# FanControllerv10.net
KiCad netlist of a schematic drawn in EAGLE
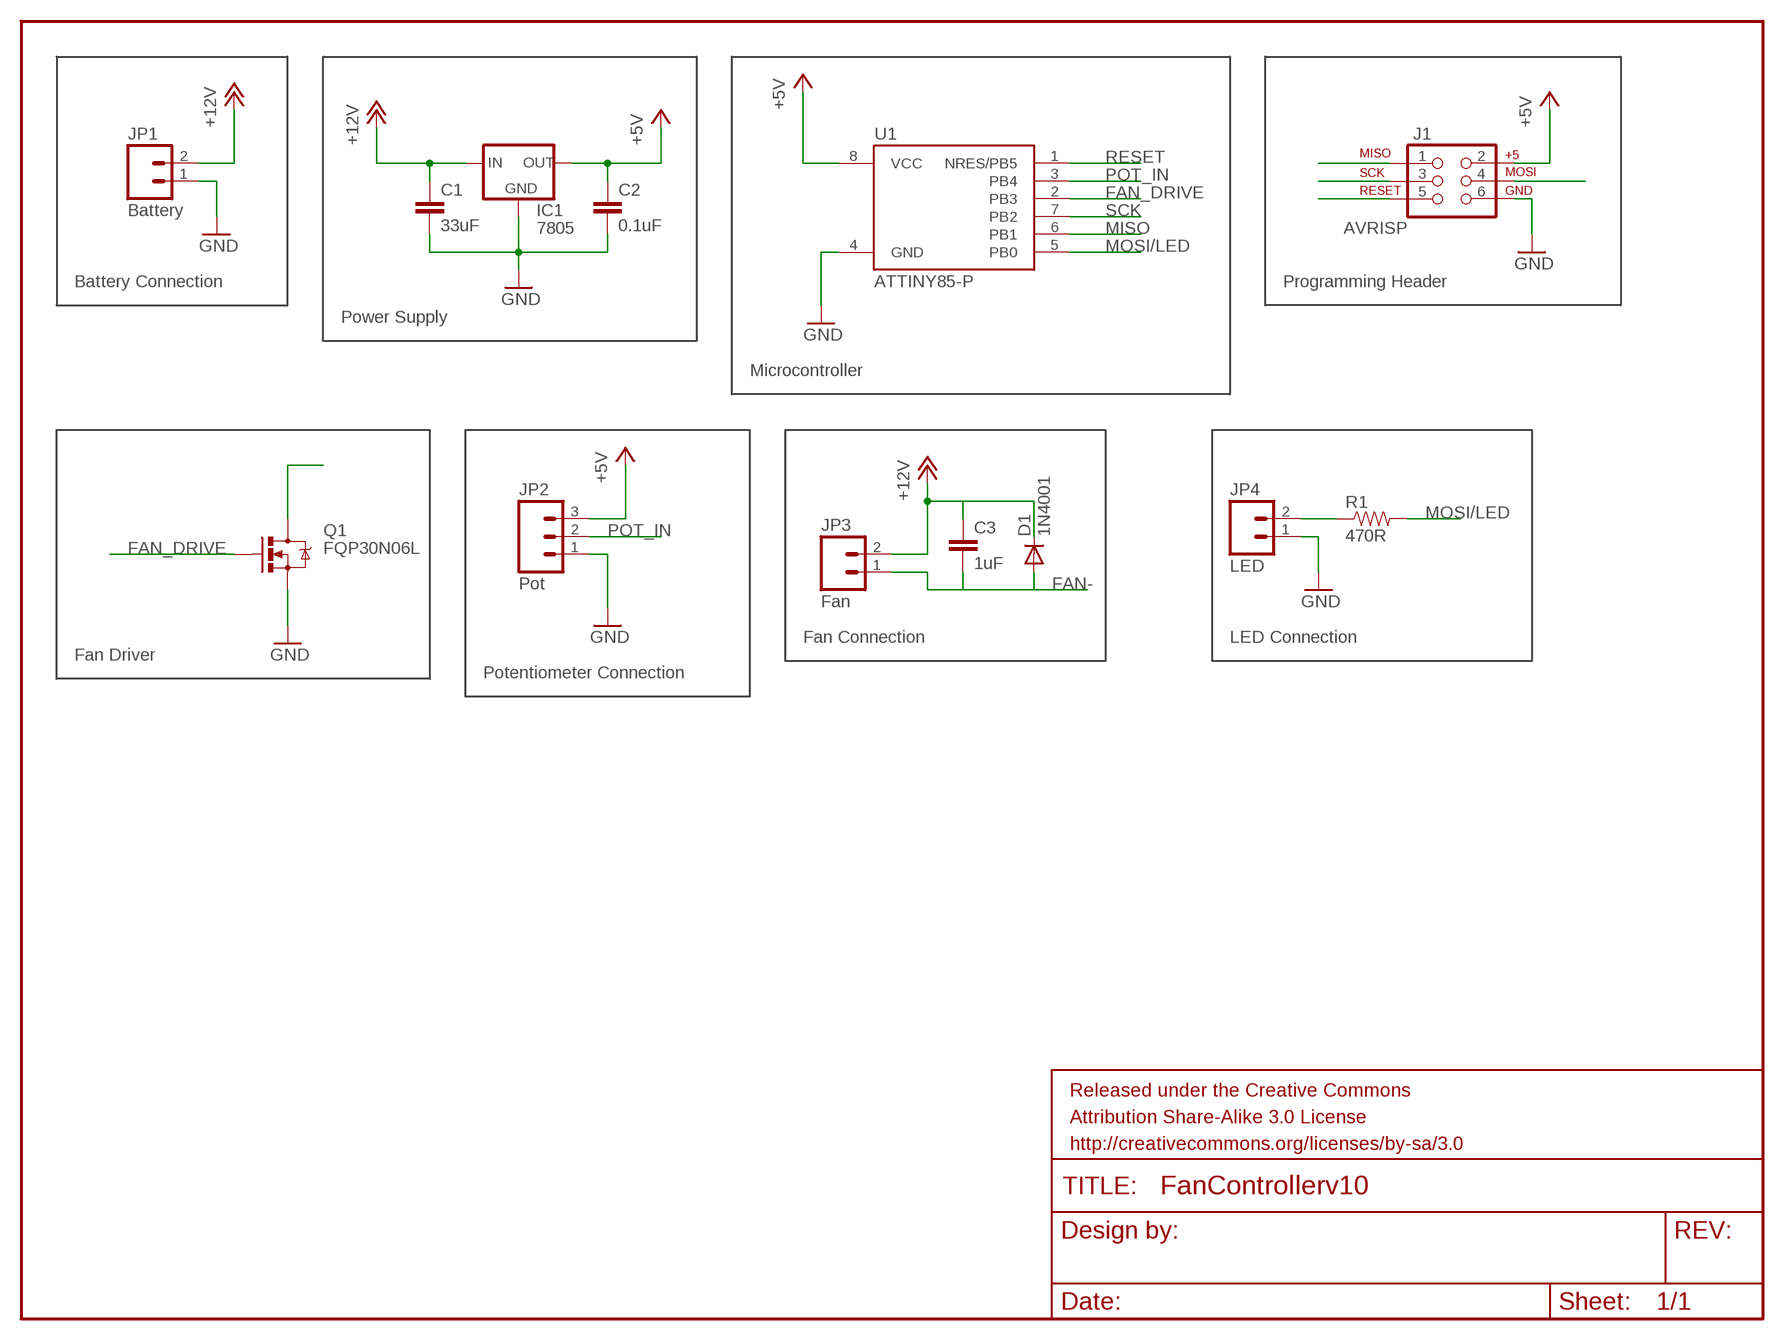
[diagram p0: schematic, sheet 1]

(export (version "E")
  (design (tool "Eeschema 10.0.6"))
  (components
    (comp (ref "C1")
      (value "33uF")
      (footprint "eagle-import:CAP-PTH-SMALL")
      (libsource (lib "eagle-import") (part "CAPPTH"))
    )
    (comp (ref "C2")
      (value "0.1uF")
      (footprint "eagle-import:CAP-PTH-SMALL")
      (libsource (lib "eagle-import") (part "CAPPTH"))
    )
    (comp (ref "C3")
      (value "1uF")
      (footprint "eagle-import:CAP-PTH-SMALL")
      (libsource (lib "eagle-import") (part "CAPPTH"))
    )
    (comp (ref "D1")
      (value "1N4001")
      (footprint "eagle-import:DIODE-1N4148")
      (libsource (lib "eagle-import") (part "DIODE1N4148"))
    )
    (comp (ref "FRAME1")
      (value "FRAME-LETTER")
      (footprint "eagle-import:CREATIVE_COMMONS")
      (libsource (lib "eagle-import") (part "FRAME-LETTER"))
    )
    (comp (ref "IC1")
      (value "7805")
      (footprint "eagle-import:78XXL")
      (libsource (lib "eagle-import") (part "V_REG_78XXSIDE"))
    )
    (comp (ref "J1")
      (value "AVRISP")
      (footprint "eagle-import:2X3")
      (libsource (lib "eagle-import") (part "AVR_SPI_PRG_6PTH"))
    )
    (comp (ref "JP1")
      (value "Battery")
      (footprint "eagle-import:1X02")
      (libsource (lib "eagle-import") (part "M02PTH"))
    )
    (comp (ref "JP2")
      (value "Pot")
      (footprint "eagle-import:1X03")
      (libsource (lib "eagle-import") (part "M03PTH"))
    )
    (comp (ref "JP3")
      (value "Fan")
      (footprint "eagle-import:1X02")
      (libsource (lib "eagle-import") (part "M02PTH"))
    )
    (comp (ref "JP4")
      (value "LED")
      (footprint "eagle-import:1X02")
      (libsource (lib "eagle-import") (part "M02PTH"))
    )
    (comp (ref "Q1")
      (value "FQP30N06L")
      (footprint "eagle-import:TO220V")
      (libsource (lib "eagle-import") (part "MOSFET-NCHANNELFQP30N06L"))
    )
    (comp (ref "R1")
      (value "470R")
      (footprint "eagle-import:1206")
      (libsource (lib "eagle-import") (part "RESISTOR1206"))
    )
    (comp (ref "U1")
      (value "ATTINY85-P")
      (footprint "eagle-import:PDIP08_300MIL")
      (libsource (lib "eagle-import") (part "ATTINY85P-"))
    )
  )
  (nets
    (net (code "1") (name "+5V") (class "Default")
      (node (ref "C2") (pin "1") (pinfunction "1_1") (pintype "passive"))
      (node (ref "IC1") (pin "OUT") (pinfunction "OUT_OUT") (pintype "output"))
      (node (ref "J1") (pin "2") (pinfunction "2_2") (pintype "passive"))
      (node (ref "JP2") (pin "3") (pinfunction "3_3") (pintype "passive"))
      (node (ref "U1") (pin "8") (pinfunction "VCC_8") (pintype "power_in"))
    )
    (net (code "2") (name "+12V") (class "Default")
      (node (ref "C1") (pin "1") (pinfunction "1_1") (pintype "passive"))
      (node (ref "C3") (pin "1") (pinfunction "1_1") (pintype "passive"))
      (node (ref "D1") (pin "C") (pinfunction "C_C") (pintype "passive"))
      (node (ref "IC1") (pin "IN") (pinfunction "IN_IN") (pintype "input"))
      (node (ref "JP1") (pin "2") (pinfunction "2_2") (pintype "passive"))
      (node (ref "JP3") (pin "2") (pinfunction "2_2") (pintype "passive"))
    )
    (net (code "3") (name "/FAN-") (class "Default")
      (node (ref "C3") (pin "2") (pinfunction "2_2") (pintype "passive"))
      (node (ref "D1") (pin "A") (pinfunction "A_A") (pintype "passive"))
      (node (ref "JP3") (pin "1") (pinfunction "1_1") (pintype "passive"))
      (node (ref "Q1") (pin "2") (pinfunction "D_2") (pintype "passive"))
    )
    (net (code "4") (name "/FAN_DRIVE") (class "Default")
      (node (ref "Q1") (pin "1") (pinfunction "G_1") (pintype "passive"))
      (node (ref "U1") (pin "2") (pinfunction "PB3_2") (pintype "bidirectional"))
    )
    (net (code "5") (name "/MISO") (class "Default")
      (node (ref "J1") (pin "1") (pinfunction "1_1") (pintype "passive"))
      (node (ref "U1") (pin "6") (pinfunction "PB1_6") (pintype "bidirectional"))
    )
    (net (code "6") (name "/MOSI{slash}LED") (class "Default")
      (node (ref "J1") (pin "4") (pinfunction "4_4") (pintype "passive"))
      (node (ref "R1") (pin "2") (pinfunction "2_2") (pintype "passive"))
      (node (ref "U1") (pin "5") (pinfunction "PB0_5") (pintype "bidirectional"))
    )
    (net (code "7") (name "/POT_IN") (class "Default")
      (node (ref "JP2") (pin "2") (pinfunction "2_2") (pintype "passive"))
      (node (ref "U1") (pin "3") (pinfunction "PB4_3") (pintype "bidirectional"))
    )
    (net (code "8") (name "/RESET") (class "Default")
      (node (ref "J1") (pin "5") (pinfunction "5_5") (pintype "passive"))
      (node (ref "U1") (pin "1") (pinfunction "NRES/PB5_1") (pintype "bidirectional"))
    )
    (net (code "9") (name "/SCK") (class "Default")
      (node (ref "J1") (pin "3") (pinfunction "3_3") (pintype "passive"))
      (node (ref "U1") (pin "7") (pinfunction "PB2_7") (pintype "bidirectional"))
    )
    (net (code "10") (name "GND") (class "Default")
      (node (ref "C1") (pin "2") (pinfunction "2_2") (pintype "passive"))
      (node (ref "C2") (pin "2") (pinfunction "2_2") (pintype "passive"))
      (node (ref "IC1") (pin "GND") (pinfunction "GND_GND") (pintype "input"))
      (node (ref "J1") (pin "6") (pinfunction "6_6") (pintype "passive"))
      (node (ref "JP1") (pin "1") (pinfunction "1_1") (pintype "passive"))
      (node (ref "JP2") (pin "1") (pinfunction "1_1") (pintype "passive"))
      (node (ref "JP4") (pin "1") (pinfunction "1_1") (pintype "passive"))
      (node (ref "Q1") (pin "3") (pinfunction "S_3") (pintype "passive"))
      (node (ref "U1") (pin "4") (pinfunction "GND_4") (pintype "power_in"))
    )
    (net (code "11") (name "Net-(JP4-Pad2)") (class "Default")
      (node (ref "JP4") (pin "2") (pinfunction "2_2") (pintype "passive"))
      (node (ref "R1") (pin "1") (pinfunction "1_1") (pintype "passive"))
    )
  )
)
